# USBFeederPCB.net
KiCad netlist of a schematic drawn in EAGLE
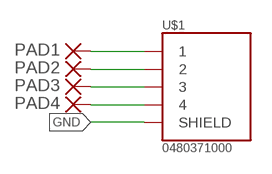
[diagram p0: schematic, sheet 1]

(export (version "E")
  (design (tool "Eeschema 10.0.6"))
  (components
    (comp (ref "PAD1")
      (value "SMD2")
      (footprint "eagle-import:SMD1,27-2,54")
      (libsource (lib "eagle-import") (part "SMD2"))
    )
    (comp (ref "PAD2")
      (value "SMD2")
      (footprint "eagle-import:SMD1,27-2,54")
      (libsource (lib "eagle-import") (part "SMD2"))
    )
    (comp (ref "PAD3")
      (value "SMD2")
      (footprint "eagle-import:SMD1,27-2,54")
      (libsource (lib "eagle-import") (part "SMD2"))
    )
    (comp (ref "PAD4")
      (value "SMD2")
      (footprint "eagle-import:SMD1,27-2,54")
      (libsource (lib "eagle-import") (part "SMD2"))
    )
    (comp (ref "U$1")
      (value "0480371000")
      (footprint "eagle-import:0480371000")
      (libsource (lib "eagle-import") (part "0480371000"))
    )
  )
  (nets
    (net (code "1") (name "GND") (class "Default")
      (node (ref "U$1") (pin "SHIELD1") (pinfunction "SHIELD_SHIELD1") (pintype "bidirectional"))
      (node (ref "U$1") (pin "SHIELD2") (pinfunction "SHIELD_SHIELD2") (pintype "bidirectional"))
    )
    (net (code "2") (name "Net-(PAD1-P)") (class "Default")
      (node (ref "PAD1") (pin "1") (pinfunction "P_1") (pintype "passive"))
      (node (ref "U$1") (pin "1") (pinfunction "1_1") (pintype "bidirectional"))
    )
    (net (code "3") (name "Net-(PAD2-P)") (class "Default")
      (node (ref "PAD2") (pin "1") (pinfunction "P_1") (pintype "passive"))
      (node (ref "U$1") (pin "2") (pinfunction "2_2") (pintype "bidirectional"))
    )
    (net (code "4") (name "Net-(PAD3-P)") (class "Default")
      (node (ref "PAD3") (pin "1") (pinfunction "P_1") (pintype "passive"))
      (node (ref "U$1") (pin "3") (pinfunction "3_3") (pintype "bidirectional"))
    )
    (net (code "5") (name "Net-(PAD4-P)") (class "Default")
      (node (ref "PAD4") (pin "1") (pinfunction "P_1") (pintype "passive"))
      (node (ref "U$1") (pin "4") (pinfunction "4_4") (pintype "bidirectional"))
    )
  )
)
